# 1_uC.net
KiCad netlist of a schematic drawn in Altium Designer
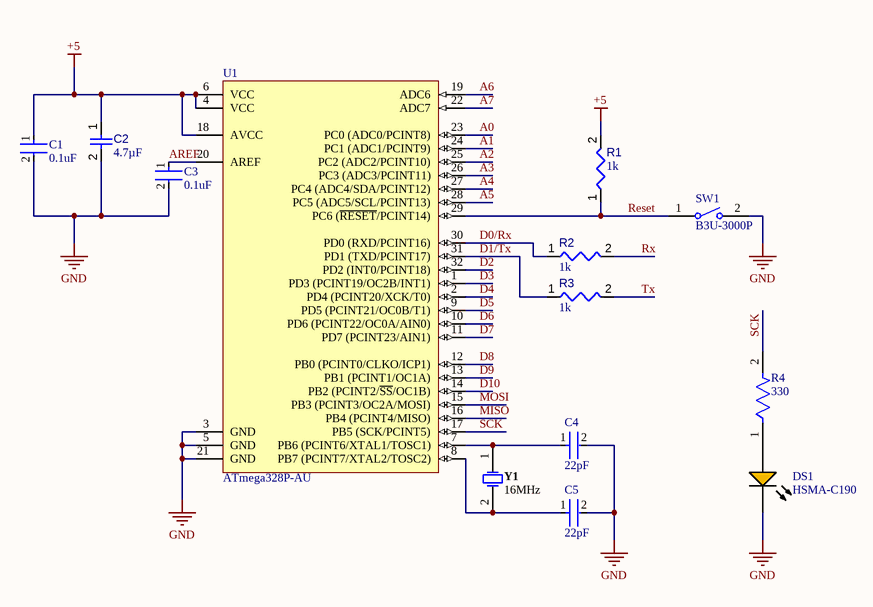
[diagram p0: 1_uC.SchDoc]

(export (version "E")
  (design (tool "Eeschema 10.0.6"))
  (components
    (comp (ref "C1")
      (value "0.1uF")
      (footprint "FP-C0805C-DN-MFG")
      (description "C0805 0.10 μF X7R 30ppm/°C 20.00% 50 V")
      (fields
        (field (name "MANUFACTURER PART NUMBER") "C0805C104M5RAC")
        (field (name "MANUFACTURER") "KEMET")
      )
      (libsource (lib "Altium Content Vault") (part "b4654b650e69147ec39a6b967a45e02"))
    )
    (comp (ref "C2")
      (value "4.7µF")
      (footprint "CAPC0805(2012)145_L")
      (description "Chip Capacitor, 4.7µF +/-40%, 25V, 0805, Thickness 1.45 mm")
      (fields (field (name "TOLERANCE") "20%") (field (name "Comment") "Capacitor 4.7µF +/-40% 25V 0805"))
      (libsource (lib "Hochschule Ravensburg Weingarten") (part "CAP-NP-2"))
    )
    (comp (ref "C3")
      (value "0.1uF")
      (footprint "FP-C0805C-DN-MFG")
      (description "C0805 0.10 μF X7R 30ppm/°C 20.00% 50 V")
      (fields
        (field (name "MANUFACTURER PART NUMBER") "C0805C104M5RAC")
        (field (name "MANUFACTURER") "KEMET")
      )
      (libsource (lib "Altium Content Vault") (part "b4654b650e69147ec39a6b967a45e02"))
    )
    (comp (ref "C4")
      (value "22pF")
      (footprint "FP-C0805C-DN-MFG")
      (description "C0805 22 pF X8R 30ppm/°C 5.00% 50 V")
      (fields
        (field (name "OCTOPART") "https://octopart.com/c0805c220j5hactu-kemet-88697040")
        (field (name "MANUFACTURER") "KEMET")
      )
      (libsource (lib "Altium Content Vault") (part "b4654b650e69147ec39a6b967a45e02"))
    )
    (comp (ref "C5")
      (value "22pF")
      (footprint "FP-C0805C-DN-MFG")
      (description "C0805 22 pF X8R 30ppm/°C 5.00% 50 V")
      (fields
        (field (name "OCTOPART") "https://octopart.com/c0805c220j5hactu-kemet-88697040")
        (field (name "MANUFACTURER") "KEMET")
      )
      (libsource (lib "Altium Content Vault") (part "b4654b650e69147ec39a6b967a45e02"))
    )
    (comp (ref "DS1")
      (value "HSMA-C190")
      (footprint "AVAG-HSMX-C190_V")
      (description "LED Uni-Color Amber, 60 mW, 20 mA, -40 to 85 degC, 2-Pin SMD, RoHS, Tape and Reel")
      (fields (field (name "POWER") "60mW") (field (name "MANUFACTURER") "Avago"))
      (libsource (lib "Hochschule Ravensburg Weingarten") (part "LED-AMBER-AK-2"))
    )
    (comp (ref "R1")
      (value "1k")
      (footprint "RESC0805(2012)_L")
      (description "1K 0.125W 5% 0805 (2012 Metric)  SMD")
      (fields (field (name "TOLERANCE") "5%") (field (name "POWER") "125mW"))
      (libsource (lib "Hochschule Ravensburg Weingarten") (part "1KR5J"))
    )
    (comp (ref "R2")
      (value "1k")
      (footprint "RESC0805(2012)_L")
      (description "1K 0.125W 5% 0805 (2012 Metric)  SMD")
      (fields (field (name "TOLERANCE") "5%") (field (name "POWER") "125mW"))
      (libsource (lib "Hochschule Ravensburg Weingarten") (part "1KR5J"))
    )
    (comp (ref "R3")
      (value "1k")
      (footprint "RESC0805(2012)_L")
      (description "1K 0.125W 5% 0805 (2012 Metric)  SMD")
      (fields (field (name "TOLERANCE") "5%") (field (name "POWER") "125mW"))
      (libsource (lib "Hochschule Ravensburg Weingarten") (part "1KR5J"))
    )
    (comp (ref "R4")
      (value "330")
      (footprint "FP-CRCW0805-e3-MFG")
      (description "RES Thick Film, 330Ω, 1%, 0.125W, 100ppm/°C, 0805")
      (fields (field (name "TOLERANCE") "1%"))
      (libsource (lib "Altium Content Vault") (part "1029c3af85768c4190bb7ad29bc67b5"))
    )
    (comp (ref "SW1")
      (value "B3U-3000P")
      (footprint "OMRON-B3U-3000P_V")
      (description "Tactile Switch, SPST-NO, 0.05 A, 12 V, -25 to 70 degC, 2-Pin SMD, RoHS, Tape and Reel")
      (fields (field (name "MANUFACTURER") "Omron Electronic Components"))
      (libsource (lib "Hochschule Ravensburg Weingarten") (part "SW-SPST-2_C"))
    )
    (comp (ref "U1")
      (value "ATmega328P-AU")
      (footprint "32A_M")
      (libsource (lib "Altium Content Vault") (part "MC-8B-ATM48-SQ32"))
    )
    (comp (ref "Y1")
      (value "16MHz")
      (footprint "JPY-X053201602002_V")
      (description "SMD Crystal, 16 MHz, +/- 20 ppm, 8 pF, -20 to 70 degC, 2-Pin SMD")
      (fields (field (name "MANUFACTURER") "Shenzhen Jingpengyuan"))
      (libsource (lib "Hochschule Ravensburg Weingarten") (part "XTAL-1-2-2"))
    )
  )
  (nets
    (net (code "1") (name "+5") (class "Default")
      (node (ref "C1") (pin "1") (pinfunction "1_1") (pintype "passive"))
      (node (ref "C2") (pin "1") (pinfunction "1_1") (pintype "passive"))
      (node (ref "R1") (pin "2") (pinfunction "2_2") (pintype "passive"))
      (node (ref "U1") (pin "18") (pinfunction "AVCC_18") (pintype "power_in"))
      (node (ref "U1") (pin "4") (pinfunction "VCC_4") (pintype "power_in"))
      (node (ref "U1") (pin "6") (pinfunction "VCC_6") (pintype "power_in"))
    )
    (net (code "2") (name "/A0") (class "Default")
      (node (ref "U1") (pin "23") (pinfunction "PC0_(ADC0/PCINT8)_23") (pintype "bidirectional"))
    )
    (net (code "3") (name "/A1") (class "Default")
      (node (ref "U1") (pin "24") (pinfunction "PC1_(ADC1/PCINT9)_24") (pintype "bidirectional"))
    )
    (net (code "4") (name "/A2") (class "Default")
      (node (ref "U1") (pin "25") (pinfunction "PC2_(ADC2/PCINT10)_25") (pintype "bidirectional"))
    )
    (net (code "5") (name "/A3") (class "Default")
      (node (ref "U1") (pin "26") (pinfunction "PC3_(ADC3/PCINT11)_26") (pintype "bidirectional"))
    )
    (net (code "6") (name "/A4") (class "Default")
      (node (ref "U1") (pin "27") (pinfunction "PC4_(ADC4/SDA/PCINT12)_27") (pintype "bidirectional"))
    )
    (net (code "7") (name "/A5") (class "Default")
      (node (ref "U1") (pin "28") (pinfunction "PC5_(ADC5/SCL/PCINT13)_28") (pintype "bidirectional"))
    )
    (net (code "8") (name "/A6") (class "Default")
      (node (ref "U1") (pin "19") (pinfunction "ADC6_19") (pintype "input"))
    )
    (net (code "9") (name "/A7") (class "Default")
      (node (ref "U1") (pin "22") (pinfunction "ADC7_22") (pintype "input"))
    )
    (net (code "10") (name "/AREF") (class "Default")
      (node (ref "C3") (pin "1") (pinfunction "1_1") (pintype "passive"))
      (node (ref "U1") (pin "20") (pinfunction "AREF_20") (pintype "passive"))
    )
    (net (code "11") (name "/D0{slash}Rx") (class "Default")
      (node (ref "R2") (pin "1") (pinfunction "1_1") (pintype "passive"))
      (node (ref "U1") (pin "30") (pinfunction "PD0_(RXD/PCINT16)_30") (pintype "bidirectional"))
    )
    (net (code "12") (name "/D1{slash}Tx") (class "Default")
      (node (ref "R3") (pin "1") (pinfunction "1_1") (pintype "passive"))
      (node (ref "U1") (pin "31") (pinfunction "PD1_(TXD/PCINT17)_31") (pintype "bidirectional"))
    )
    (net (code "13") (name "/D2") (class "Default")
      (node (ref "U1") (pin "32") (pinfunction "PD2_(INT0/PCINT18)_32") (pintype "bidirectional"))
    )
    (net (code "14") (name "/D3") (class "Default")
      (node (ref "U1") (pin "1") (pinfunction "PD3_(PCINT19/OC2B/INT1)_1") (pintype "bidirectional"))
    )
    (net (code "15") (name "/D4") (class "Default")
      (node (ref "U1") (pin "2") (pinfunction "PD4_(PCINT20/XCK/T0)_2") (pintype "bidirectional"))
    )
    (net (code "16") (name "/D5") (class "Default")
      (node (ref "U1") (pin "9") (pinfunction "PD5_(PCINT21/OC0B/T1)_9") (pintype "bidirectional"))
    )
    (net (code "17") (name "/D6") (class "Default")
      (node (ref "U1") (pin "10") (pinfunction "PD6_(PCINT22/OC0A/AIN0)_10") (pintype "bidirectional"))
    )
    (net (code "18") (name "/D7") (class "Default")
      (node (ref "U1") (pin "11") (pinfunction "PD7_(PCINT23/AIN1)_11") (pintype "bidirectional"))
    )
    (net (code "19") (name "/D8") (class "Default")
      (node (ref "U1") (pin "12") (pinfunction "PB0_(PCINT0/CLKO/ICP1)_12") (pintype "bidirectional"))
    )
    (net (code "20") (name "/D9") (class "Default")
      (node (ref "U1") (pin "13") (pinfunction "PB1_(PCINT1/OC1A)_13") (pintype "bidirectional"))
    )
    (net (code "21") (name "/D10") (class "Default")
      (node (ref "U1") (pin "14") (pinfunction "PB2_(PCINT2/~{SS}/OC1B)_14") (pintype "bidirectional"))
    )
    (net (code "22") (name "/MISO") (class "Default")
      (node (ref "U1") (pin "16") (pinfunction "PB4_(PCINT4/MISO)_16") (pintype "bidirectional"))
    )
    (net (code "23") (name "/MOSI") (class "Default")
      (node (ref "U1") (pin "15") (pinfunction "PB3_(PCINT3/OC2A/MOSI)_15") (pintype "bidirectional"))
    )
    (net (code "24") (name "/Reset") (class "Default")
      (node (ref "R1") (pin "1") (pinfunction "1_1") (pintype "passive"))
      (node (ref "SW1") (pin "1") (pinfunction "1_1") (pintype "passive"))
      (node (ref "U1") (pin "29") (pinfunction "PC6_(~{RESET}/PCINT14)_29") (pintype "bidirectional"))
    )
    (net (code "25") (name "/Rx") (class "Default")
      (node (ref "R2") (pin "2") (pinfunction "2_2") (pintype "passive"))
    )
    (net (code "26") (name "/SCK") (class "Default")
      (node (ref "R4") (pin "2") (pinfunction "2_2") (pintype "passive"))
      (node (ref "U1") (pin "17") (pinfunction "PB5_(SCK/PCINT5)_17") (pintype "bidirectional"))
    )
    (net (code "27") (name "/Tx") (class "Default")
      (node (ref "R3") (pin "2") (pinfunction "2_2") (pintype "passive"))
    )
    (net (code "28") (name "GND") (class "Default")
      (node (ref "C1") (pin "2") (pinfunction "2_2") (pintype "passive"))
      (node (ref "C2") (pin "2") (pinfunction "2_2") (pintype "passive"))
      (node (ref "C3") (pin "2") (pinfunction "2_2") (pintype "passive"))
      (node (ref "C4") (pin "2") (pinfunction "2_2") (pintype "passive"))
      (node (ref "C5") (pin "2") (pinfunction "2_2") (pintype "passive"))
      (node (ref "DS1") (pin "2") (pinfunction "K_2") (pintype "passive"))
      (node (ref "SW1") (pin "2") (pinfunction "2_2") (pintype "passive"))
      (node (ref "U1") (pin "21") (pinfunction "GND_21") (pintype "power_in"))
      (node (ref "U1") (pin "3") (pinfunction "GND_3") (pintype "power_in"))
      (node (ref "U1") (pin "5") (pinfunction "GND_5") (pintype "power_in"))
    )
    (net (code "29") (name "Net-(DS1-A)") (class "Default")
      (node (ref "DS1") (pin "1") (pinfunction "A_1") (pintype "passive"))
      (node (ref "R4") (pin "1") (pinfunction "1_1") (pintype "passive"))
    )
    (net (code "30") (name "Net-(U1-PB6_(PCINT6{slash}XTAL1{slash}TOSC1))") (class "Default")
      (node (ref "C4") (pin "1") (pinfunction "1_1") (pintype "passive"))
      (node (ref "U1") (pin "7") (pinfunction "PB6_(PCINT6/XTAL1/TOSC1)_7") (pintype "bidirectional"))
      (node (ref "Y1") (pin "1") (pinfunction "1_1") (pintype "passive"))
    )
    (net (code "31") (name "Net-(U1-PB7_(PCINT7{slash}XTAL2{slash}TOSC2))") (class "Default")
      (node (ref "C5") (pin "1") (pinfunction "1_1") (pintype "passive"))
      (node (ref "U1") (pin "8") (pinfunction "PB7_(PCINT7/XTAL2/TOSC2)_8") (pintype "bidirectional"))
      (node (ref "Y1") (pin "2") (pinfunction "2_2") (pintype "passive"))
    )
  )
)
